# AMC_FMC_Carrier.net
KiCad netlist of a schematic drawn in Altium Designer
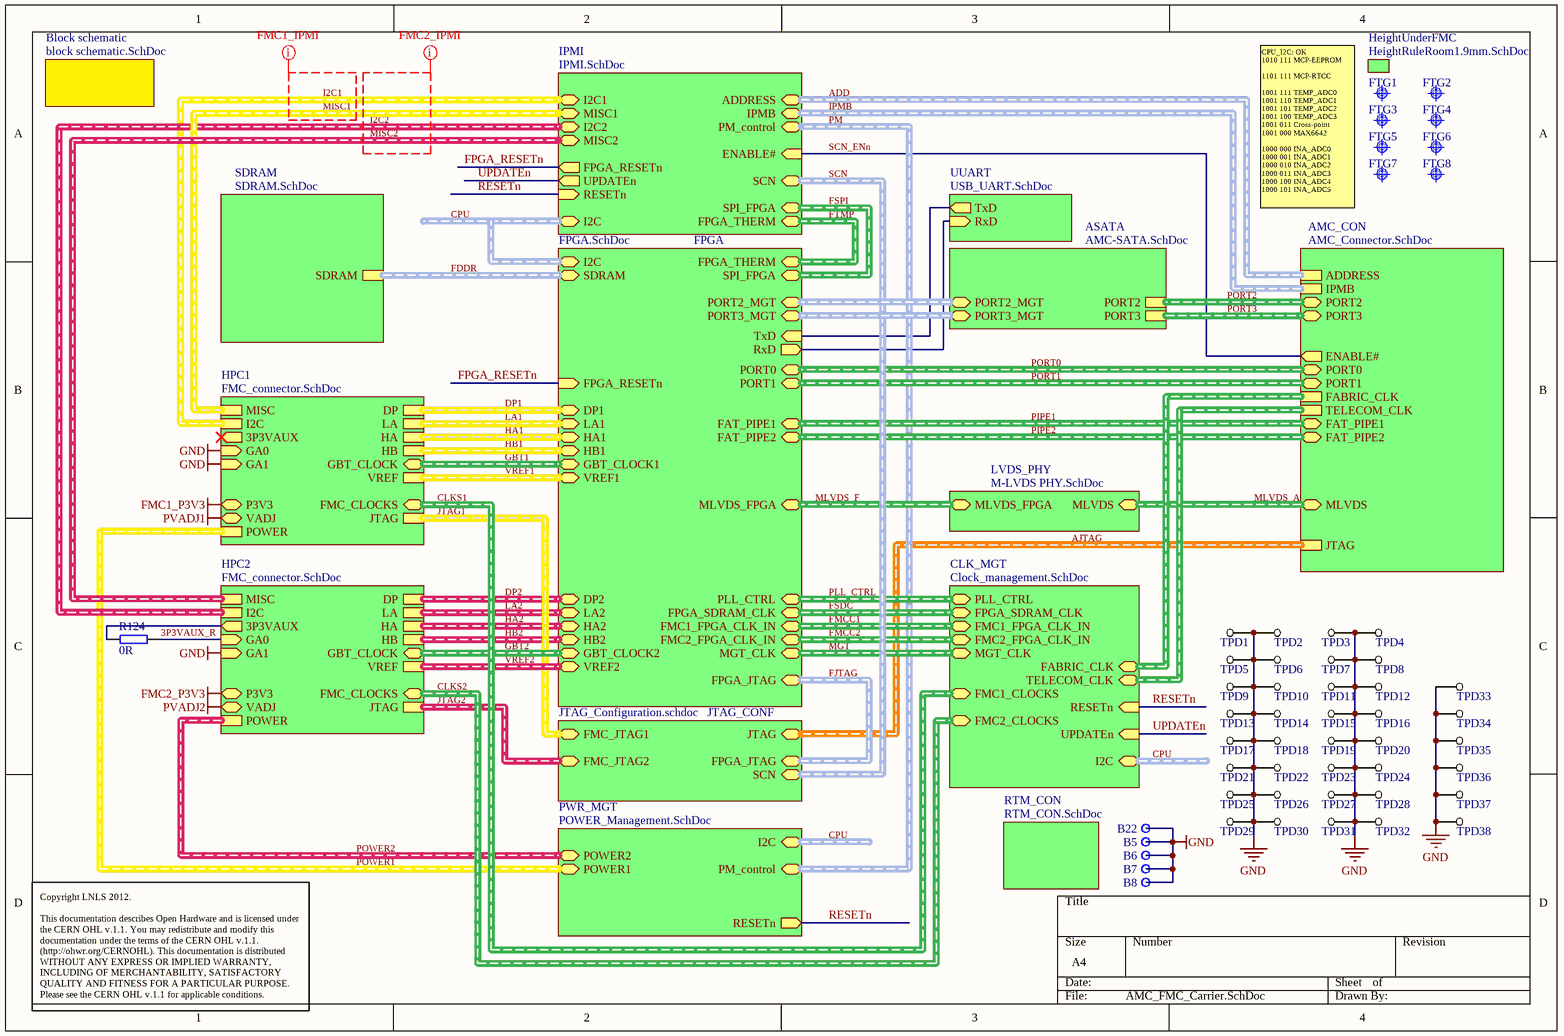
[diagram p0: AMC_FMC_Carrier.SchDoc]

(export (version "E")
  (design (tool "Eeschema 10.0.6"))
  (components
    (comp (ref "B5")
      (value "Test Point")
      (footprint "VERO_20-2136")
      (description "Single Terminal Socket")
      (fields
        (field (name "PART NUMBER") "VERO_20-2136")
        (field (name "MANUFACTURER") "VERO TECHNOLOGIES")
        (field (name "AUTHOR") "CERN DEM JLC")
      )
      (libsource (lib "Connectors") (part "Single Terminal Socket"))
    )
    (comp (ref "B6")
      (value "Test Point")
      (footprint "VERO_20-2136")
      (description "Single Terminal Socket")
      (fields
        (field (name "PART NUMBER") "VERO_20-2136")
        (field (name "MANUFACTURER") "VERO TECHNOLOGIES")
        (field (name "AUTHOR") "CERN DEM JLC")
      )
      (libsource (lib "Connectors") (part "Single Terminal Socket"))
    )
    (comp (ref "B7")
      (value "Test Point")
      (footprint "VERO_20-2136")
      (description "Single Terminal Socket")
      (fields
        (field (name "PART NUMBER") "VERO_20-2136")
        (field (name "MANUFACTURER") "VERO TECHNOLOGIES")
        (field (name "AUTHOR") "CERN DEM JLC")
      )
      (libsource (lib "Connectors") (part "Single Terminal Socket"))
    )
    (comp (ref "B8")
      (value "Test Point")
      (footprint "VERO_20-2136")
      (description "Single Terminal Socket")
      (fields
        (field (name "PART NUMBER") "VERO_20-2136")
        (field (name "MANUFACTURER") "VERO TECHNOLOGIES")
        (field (name "AUTHOR") "CERN DEM JLC")
      )
      (libsource (lib "Connectors") (part "Single Terminal Socket"))
    )
    (comp (ref "B22")
      (value "Test Point")
      (footprint "VERO_20-2136")
      (description "Single Terminal Socket")
      (fields
        (field (name "PART NUMBER") "VERO_20-2136")
        (field (name "MANUFACTURER") "VERO TECHNOLOGIES")
        (field (name "AUTHOR") "CERN DEM JLC")
      )
      (libsource (lib "Connectors") (part "Single Terminal Socket"))
    )
    (comp (ref "FTG1")
      (value "Use only in PCB")
      (footprint "FIDUCIAL_TOP_S100-200")
      (description "Fiducial Target")
      (fields (field (name "PART NUMBER") "FIDUCIAL_TARGET_S100-200") (field (name "AUTHOR") "CERN DEM JLC"))
      (libsource (lib "Eletro-mechanical") (part "Fiducial Target"))
    )
    (comp (ref "FTG2")
      (value "Use only in PCB")
      (footprint "FIDUCIAL_TOP_C100-200")
      (description "Fiducial Target")
      (fields (field (name "PART NUMBER") "FIDUCIAL_TARGET_C100-200") (field (name "AUTHOR") "CERN DEM JLC"))
      (libsource (lib "Eletro-mechanical") (part "Fiducial Target"))
    )
    (comp (ref "FTG3")
      (value "Use only in PCB")
      (footprint "FIDUCIAL_TOP_S100-200")
      (description "Fiducial Target")
      (fields (field (name "PART NUMBER") "FIDUCIAL_TARGET_S100-200") (field (name "AUTHOR") "CERN DEM JLC"))
      (libsource (lib "Eletro-mechanical") (part "Fiducial Target"))
    )
    (comp (ref "FTG4")
      (value "Use only in PCB")
      (footprint "FIDUCIAL_TOP_C100-200")
      (description "Fiducial Target")
      (fields (field (name "PART NUMBER") "FIDUCIAL_TARGET_C100-200") (field (name "AUTHOR") "CERN DEM JLC"))
      (libsource (lib "Eletro-mechanical") (part "Fiducial Target"))
    )
    (comp (ref "FTG5")
      (value "Use only in PCB")
      (footprint "FIDUCIAL_TOP_S100-200")
      (description "Fiducial Target")
      (fields (field (name "PART NUMBER") "FIDUCIAL_TARGET_S100-200") (field (name "AUTHOR") "CERN DEM JLC"))
      (libsource (lib "Eletro-mechanical") (part "Fiducial Target"))
    )
    (comp (ref "FTG6")
      (value "Use only in PCB")
      (footprint "FIDUCIAL_TOP_C100-200")
      (description "Fiducial Target")
      (fields (field (name "PART NUMBER") "FIDUCIAL_TARGET_C100-200") (field (name "AUTHOR") "CERN DEM JLC"))
      (libsource (lib "Eletro-mechanical") (part "Fiducial Target"))
    )
    (comp (ref "FTG7")
      (value "Use only in PCB")
      (footprint "FIDUCIAL_TOP_S100-200")
      (description "Fiducial Target")
      (fields (field (name "PART NUMBER") "FIDUCIAL_TARGET_S100-200") (field (name "AUTHOR") "CERN DEM JLC"))
      (libsource (lib "Eletro-mechanical") (part "Fiducial Target"))
    )
    (comp (ref "FTG8")
      (value "Use only in PCB")
      (footprint "FIDUCIAL_TOP_C100-200")
      (description "Fiducial Target")
      (fields (field (name "PART NUMBER") "FIDUCIAL_TARGET_C100-200") (field (name "AUTHOR") "CERN DEM JLC"))
      (libsource (lib "Eletro-mechanical") (part "Fiducial Target"))
    )
    (comp (ref "R124")
      (value "0R")
      (footprint "0402R")
      (description "SMD Resistor")
      (libsource (lib "LIBRARY_SCH") (part "RES_0402"))
    )
    (comp (ref "TPD1")
      (value "Test Point")
      (footprint "TP_DIFF_0805")
      (description "1625854-2")
      (fields (field (name "PART NUMBER") "TP_DIFF"))
      (libsource (lib "Markers") (part "TP_SMD_DIFF"))
    )
    (comp (ref "TPD2")
      (value "Test Point")
      (footprint "TP_DIFF_0805")
      (description "1625854-2")
      (fields (field (name "PART NUMBER") "TP_DIFF"))
      (libsource (lib "Markers") (part "TP_SMD_DIFF"))
    )
    (comp (ref "TPD3")
      (value "Test Point")
      (footprint "TP_DIFF_0805")
      (description "1625854-2")
      (fields (field (name "PART NUMBER") "TP_DIFF"))
      (libsource (lib "Markers") (part "TP_SMD_DIFF"))
    )
    (comp (ref "TPD4")
      (value "Test Point")
      (footprint "TP_DIFF_0805")
      (description "1625854-2")
      (fields (field (name "PART NUMBER") "TP_DIFF"))
      (libsource (lib "Markers") (part "TP_SMD_DIFF"))
    )
    (comp (ref "TPD5")
      (value "Test Point")
      (footprint "TP_DIFF_0805")
      (description "1625854-2")
      (fields (field (name "PART NUMBER") "TP_DIFF"))
      (libsource (lib "Markers") (part "TP_SMD_DIFF"))
    )
    (comp (ref "TPD6")
      (value "Test Point")
      (footprint "TP_DIFF_0805")
      (description "1625854-2")
      (fields (field (name "PART NUMBER") "TP_DIFF"))
      (libsource (lib "Markers") (part "TP_SMD_DIFF"))
    )
    (comp (ref "TPD7")
      (value "Test Point")
      (footprint "TP_DIFF_0805")
      (description "1625854-2")
      (fields (field (name "PART NUMBER") "TP_DIFF"))
      (libsource (lib "Markers") (part "TP_SMD_DIFF"))
    )
    (comp (ref "TPD8")
      (value "Test Point")
      (footprint "TP_DIFF_0805")
      (description "1625854-2")
      (fields (field (name "PART NUMBER") "TP_DIFF"))
      (libsource (lib "Markers") (part "TP_SMD_DIFF"))
    )
    (comp (ref "TPD9")
      (value "Test Point")
      (footprint "TP_DIFF_0805")
      (description "1625854-2")
      (fields (field (name "PART NUMBER") "TP_DIFF"))
      (libsource (lib "Markers") (part "TP_SMD_DIFF"))
    )
    (comp (ref "TPD10")
      (value "Test Point")
      (footprint "TP_DIFF_0805")
      (description "1625854-2")
      (fields (field (name "PART NUMBER") "TP_DIFF"))
      (libsource (lib "Markers") (part "TP_SMD_DIFF"))
    )
    (comp (ref "TPD11")
      (value "Test Point")
      (footprint "TP_DIFF_0805")
      (description "1625854-2")
      (fields (field (name "PART NUMBER") "TP_DIFF"))
      (libsource (lib "Markers") (part "TP_SMD_DIFF"))
    )
    (comp (ref "TPD12")
      (value "Test Point")
      (footprint "TP_DIFF_0805")
      (description "1625854-2")
      (fields (field (name "PART NUMBER") "TP_DIFF"))
      (libsource (lib "Markers") (part "TP_SMD_DIFF"))
    )
    (comp (ref "TPD13")
      (value "Test Point")
      (footprint "TP_DIFF_0805")
      (description "1625854-2")
      (fields (field (name "PART NUMBER") "TP_DIFF"))
      (libsource (lib "Markers") (part "TP_SMD_DIFF"))
    )
    (comp (ref "TPD14")
      (value "Test Point")
      (footprint "TP_DIFF_0805")
      (description "1625854-2")
      (fields (field (name "PART NUMBER") "TP_DIFF"))
      (libsource (lib "Markers") (part "TP_SMD_DIFF"))
    )
    (comp (ref "TPD15")
      (value "Test Point")
      (footprint "TP_DIFF_0805")
      (description "1625854-2")
      (fields (field (name "PART NUMBER") "TP_DIFF"))
      (libsource (lib "Markers") (part "TP_SMD_DIFF"))
    )
    (comp (ref "TPD16")
      (value "Test Point")
      (footprint "TP_DIFF_0805")
      (description "1625854-2")
      (fields (field (name "PART NUMBER") "TP_DIFF"))
      (libsource (lib "Markers") (part "TP_SMD_DIFF"))
    )
    (comp (ref "TPD17")
      (value "Test Point")
      (footprint "TP_DIFF_0805")
      (description "1625854-2")
      (fields (field (name "PART NUMBER") "TP_DIFF"))
      (libsource (lib "Markers") (part "TP_SMD_DIFF"))
    )
    (comp (ref "TPD18")
      (value "Test Point")
      (footprint "TP_DIFF_0805")
      (description "1625854-2")
      (fields (field (name "PART NUMBER") "TP_DIFF"))
      (libsource (lib "Markers") (part "TP_SMD_DIFF"))
    )
    (comp (ref "TPD19")
      (value "Test Point")
      (footprint "TP_DIFF_0805")
      (description "1625854-2")
      (fields (field (name "PART NUMBER") "TP_DIFF"))
      (libsource (lib "Markers") (part "TP_SMD_DIFF"))
    )
    (comp (ref "TPD20")
      (value "Test Point")
      (footprint "TP_DIFF_0805")
      (description "1625854-2")
      (fields (field (name "PART NUMBER") "TP_DIFF"))
      (libsource (lib "Markers") (part "TP_SMD_DIFF"))
    )
    (comp (ref "TPD21")
      (value "Test Point")
      (footprint "TP_DIFF_0805")
      (description "1625854-2")
      (fields (field (name "PART NUMBER") "TP_DIFF"))
      (libsource (lib "Markers") (part "TP_SMD_DIFF"))
    )
    (comp (ref "TPD22")
      (value "Test Point")
      (footprint "TP_DIFF_0805")
      (description "1625854-2")
      (fields (field (name "PART NUMBER") "TP_DIFF"))
      (libsource (lib "Markers") (part "TP_SMD_DIFF"))
    )
    (comp (ref "TPD23")
      (value "Test Point")
      (footprint "TP_DIFF_0805")
      (description "1625854-2")
      (fields (field (name "PART NUMBER") "TP_DIFF"))
      (libsource (lib "Markers") (part "TP_SMD_DIFF"))
    )
    (comp (ref "TPD24")
      (value "Test Point")
      (footprint "TP_DIFF_0805")
      (description "1625854-2")
      (fields (field (name "PART NUMBER") "TP_DIFF"))
      (libsource (lib "Markers") (part "TP_SMD_DIFF"))
    )
    (comp (ref "TPD25")
      (value "Test Point")
      (footprint "TP_DIFF_0805")
      (description "1625854-2")
      (fields (field (name "PART NUMBER") "TP_DIFF"))
      (libsource (lib "Markers") (part "TP_SMD_DIFF"))
    )
    (comp (ref "TPD26")
      (value "Test Point")
      (footprint "TP_DIFF_0805")
      (description "1625854-2")
      (fields (field (name "PART NUMBER") "TP_DIFF"))
      (libsource (lib "Markers") (part "TP_SMD_DIFF"))
    )
    (comp (ref "TPD27")
      (value "Test Point")
      (footprint "TP_DIFF_0805")
      (description "1625854-2")
      (fields (field (name "PART NUMBER") "TP_DIFF"))
      (libsource (lib "Markers") (part "TP_SMD_DIFF"))
    )
    (comp (ref "TPD28")
      (value "Test Point")
      (footprint "TP_DIFF_0805")
      (description "1625854-2")
      (fields (field (name "PART NUMBER") "TP_DIFF"))
      (libsource (lib "Markers") (part "TP_SMD_DIFF"))
    )
    (comp (ref "TPD29")
      (value "Test Point")
      (footprint "TP_DIFF_0805")
      (description "1625854-2")
      (fields (field (name "PART NUMBER") "TP_DIFF"))
      (libsource (lib "Markers") (part "TP_SMD_DIFF"))
    )
    (comp (ref "TPD30")
      (value "Test Point")
      (footprint "TP_DIFF_0805")
      (description "1625854-2")
      (fields (field (name "PART NUMBER") "TP_DIFF"))
      (libsource (lib "Markers") (part "TP_SMD_DIFF"))
    )
    (comp (ref "TPD31")
      (value "Test Point")
      (footprint "TP_DIFF_0805")
      (description "1625854-2")
      (fields (field (name "PART NUMBER") "TP_DIFF"))
      (libsource (lib "Markers") (part "TP_SMD_DIFF"))
    )
    (comp (ref "TPD32")
      (value "Test Point")
      (footprint "TP_DIFF_0805")
      (description "1625854-2")
      (fields (field (name "PART NUMBER") "TP_DIFF"))
      (libsource (lib "Markers") (part "TP_SMD_DIFF"))
    )
    (comp (ref "TPD33")
      (value "Test Point")
      (footprint "TP_DIFF_0805")
      (description "1625854-2")
      (fields (field (name "PART NUMBER") "TP_DIFF"))
      (libsource (lib "Markers") (part "TP_SMD_DIFF"))
    )
    (comp (ref "TPD34")
      (value "Test Point")
      (footprint "TP_DIFF_0805")
      (description "1625854-2")
      (fields (field (name "PART NUMBER") "TP_DIFF"))
      (libsource (lib "Markers") (part "TP_SMD_DIFF"))
    )
    (comp (ref "TPD35")
      (value "Test Point")
      (footprint "TP_DIFF_0805")
      (description "1625854-2")
      (fields (field (name "PART NUMBER") "TP_DIFF"))
      (libsource (lib "Markers") (part "TP_SMD_DIFF"))
    )
    (comp (ref "TPD36")
      (value "Test Point")
      (footprint "TP_DIFF_0805")
      (description "1625854-2")
      (fields (field (name "PART NUMBER") "TP_DIFF"))
      (libsource (lib "Markers") (part "TP_SMD_DIFF"))
    )
    (comp (ref "TPD37")
      (value "Test Point")
      (footprint "TP_DIFF_0805")
      (description "1625854-2")
      (fields (field (name "PART NUMBER") "TP_DIFF"))
      (libsource (lib "Markers") (part "TP_SMD_DIFF"))
    )
    (comp (ref "TPD38")
      (value "Test Point")
      (footprint "TP_DIFF_0805")
      (description "1625854-2")
      (fields (field (name "PART NUMBER") "TP_DIFF"))
      (libsource (lib "Markers") (part "TP_SMD_DIFF"))
    )
  )
  (nets
    (net (code "46") (name "/3P3VAUX") (class "Default")
      (node (ref "R124") (pin "1") (pinfunction "1_1") (pintype "passive"))
    )
    (net (code "48") (name "/3P3VAUX_R") (class "Default")
      (node (ref "R124") (pin "2") (pinfunction "2_2") (pintype "passive"))
    )
    (net (code "107") (name "GND") (class "Default")
      (node (ref "B22") (pin "1") (pinfunction "1_1") (pintype "bidirectional"))
      (node (ref "B5") (pin "1") (pinfunction "1_1") (pintype "bidirectional"))
      (node (ref "B6") (pin "1") (pinfunction "1_1") (pintype "bidirectional"))
      (node (ref "B7") (pin "1") (pinfunction "1_1") (pintype "bidirectional"))
      (node (ref "B8") (pin "1") (pinfunction "1_1") (pintype "bidirectional"))
      (node (ref "TPD1") (pin "1") (pinfunction "TP_1") (pintype "passive"))
      (node (ref "TPD10") (pin "1") (pinfunction "TP_1") (pintype "passive"))
      (node (ref "TPD11") (pin "1") (pinfunction "TP_1") (pintype "passive"))
      (node (ref "TPD12") (pin "1") (pinfunction "TP_1") (pintype "passive"))
      (node (ref "TPD13") (pin "1") (pinfunction "TP_1") (pintype "passive"))
      (node (ref "TPD14") (pin "1") (pinfunction "TP_1") (pintype "passive"))
      (node (ref "TPD15") (pin "1") (pinfunction "TP_1") (pintype "passive"))
      (node (ref "TPD16") (pin "1") (pinfunction "TP_1") (pintype "passive"))
      (node (ref "TPD17") (pin "1") (pinfunction "TP_1") (pintype "passive"))
      (node (ref "TPD18") (pin "1") (pinfunction "TP_1") (pintype "passive"))
      (node (ref "TPD19") (pin "1") (pinfunction "TP_1") (pintype "passive"))
      (node (ref "TPD2") (pin "1") (pinfunction "TP_1") (pintype "passive"))
      (node (ref "TPD20") (pin "1") (pinfunction "TP_1") (pintype "passive"))
      (node (ref "TPD21") (pin "1") (pinfunction "TP_1") (pintype "passive"))
      (node (ref "TPD22") (pin "1") (pinfunction "TP_1") (pintype "passive"))
      (node (ref "TPD23") (pin "1") (pinfunction "TP_1") (pintype "passive"))
      (node (ref "TPD24") (pin "1") (pinfunction "TP_1") (pintype "passive"))
      (node (ref "TPD25") (pin "1") (pinfunction "TP_1") (pintype "passive"))
      (node (ref "TPD26") (pin "1") (pinfunction "TP_1") (pintype "passive"))
      (node (ref "TPD27") (pin "1") (pinfunction "TP_1") (pintype "passive"))
      (node (ref "TPD28") (pin "1") (pinfunction "TP_1") (pintype "passive"))
      (node (ref "TPD29") (pin "1") (pinfunction "TP_1") (pintype "passive"))
      (node (ref "TPD3") (pin "1") (pinfunction "TP_1") (pintype "passive"))
      (node (ref "TPD30") (pin "1") (pinfunction "TP_1") (pintype "passive"))
      (node (ref "TPD31") (pin "1") (pinfunction "TP_1") (pintype "passive"))
      (node (ref "TPD32") (pin "1") (pinfunction "TP_1") (pintype "passive"))
      (node (ref "TPD33") (pin "1") (pinfunction "TP_1") (pintype "passive"))
      (node (ref "TPD34") (pin "1") (pinfunction "TP_1") (pintype "passive"))
      (node (ref "TPD35") (pin "1") (pinfunction "TP_1") (pintype "passive"))
      (node (ref "TPD36") (pin "1") (pinfunction "TP_1") (pintype "passive"))
      (node (ref "TPD37") (pin "1") (pinfunction "TP_1") (pintype "passive"))
      (node (ref "TPD38") (pin "1") (pinfunction "TP_1") (pintype "passive"))
      (node (ref "TPD4") (pin "1") (pinfunction "TP_1") (pintype "passive"))
      (node (ref "TPD5") (pin "1") (pinfunction "TP_1") (pintype "passive"))
      (node (ref "TPD6") (pin "1") (pinfunction "TP_1") (pintype "passive"))
      (node (ref "TPD7") (pin "1") (pinfunction "TP_1") (pintype "passive"))
      (node (ref "TPD8") (pin "1") (pinfunction "TP_1") (pintype "passive"))
      (node (ref "TPD9") (pin "1") (pinfunction "TP_1") (pintype "passive"))
    )
  )
)
